# Sheet.net
KiCad netlist of a schematic drawn in Altium Designer
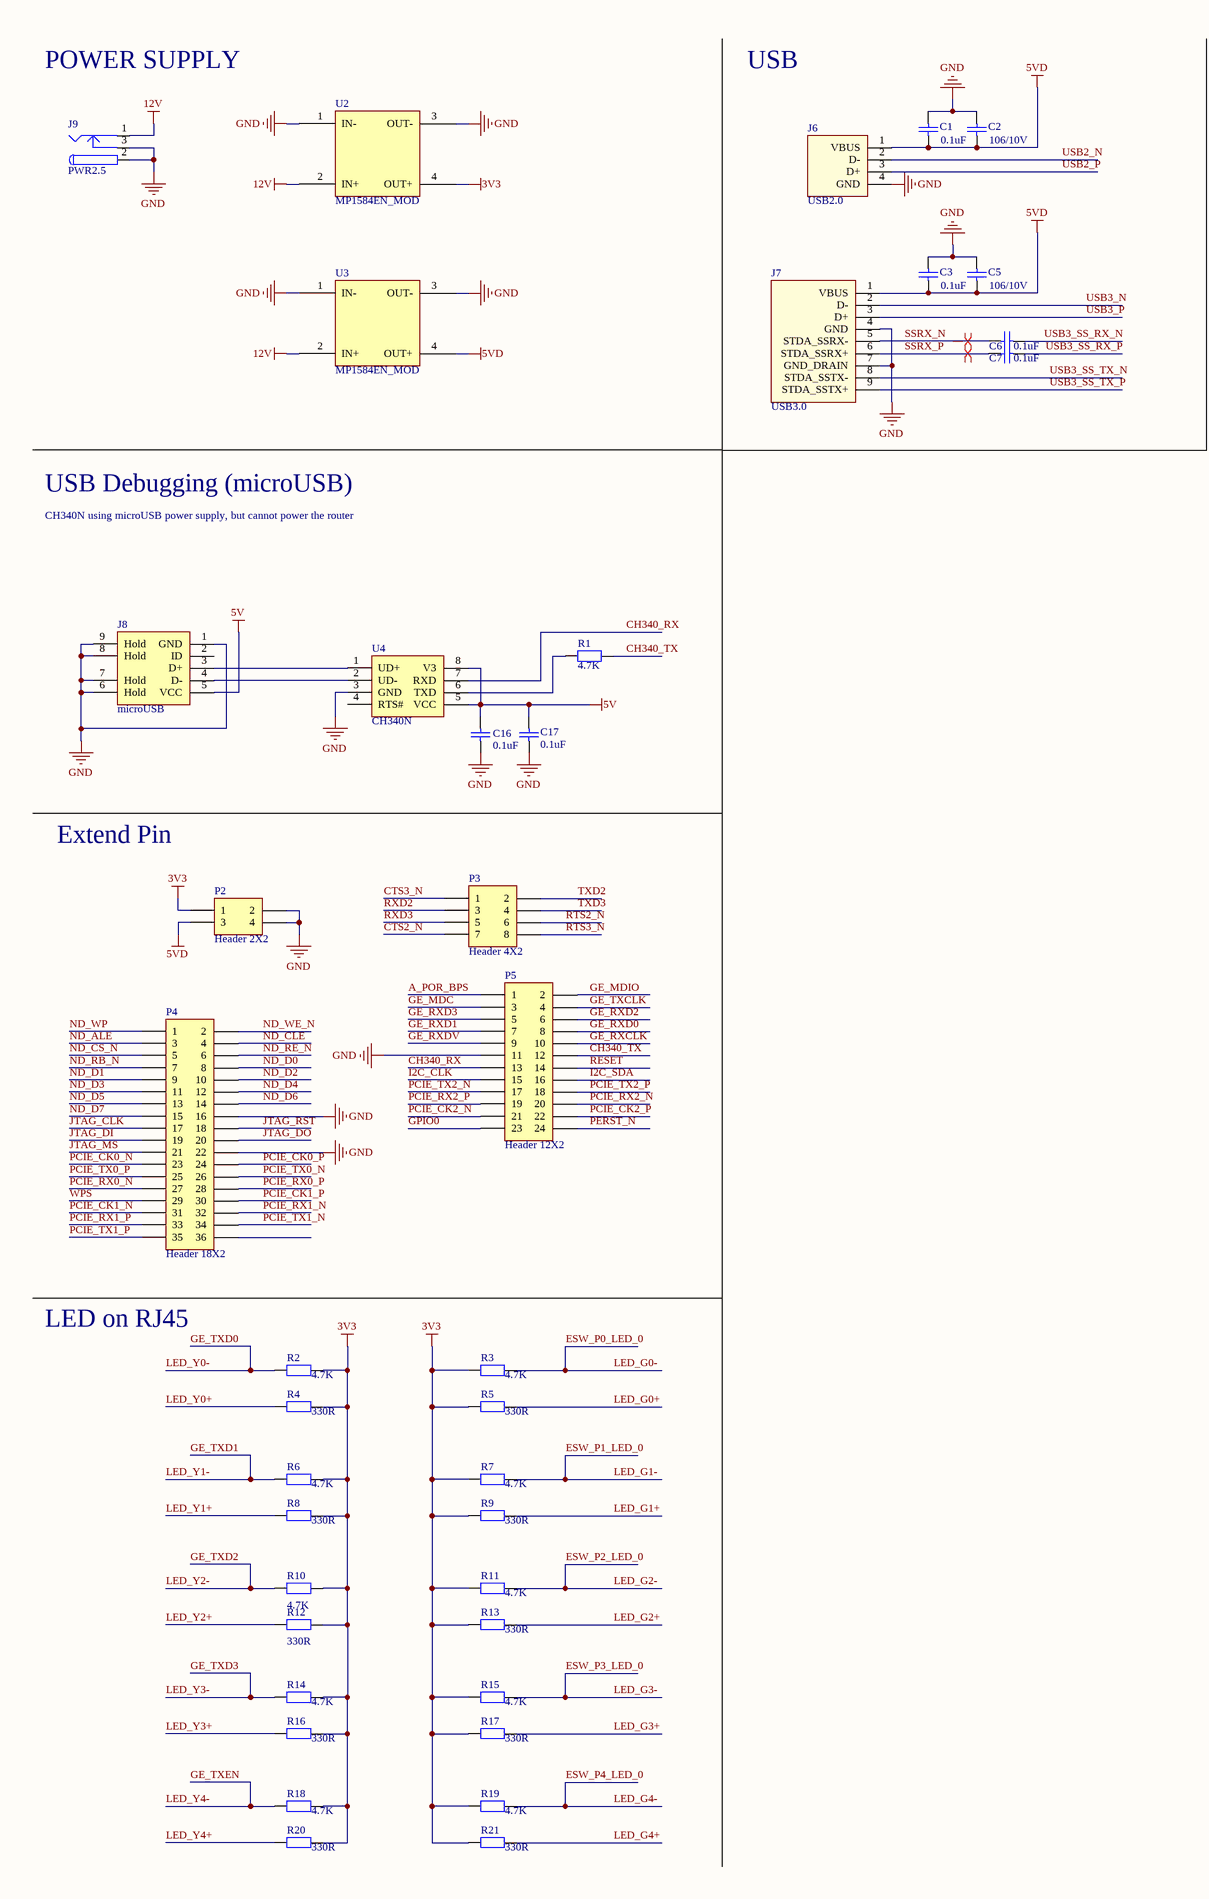
[diagram p0: Sheet.SchDoc, left]
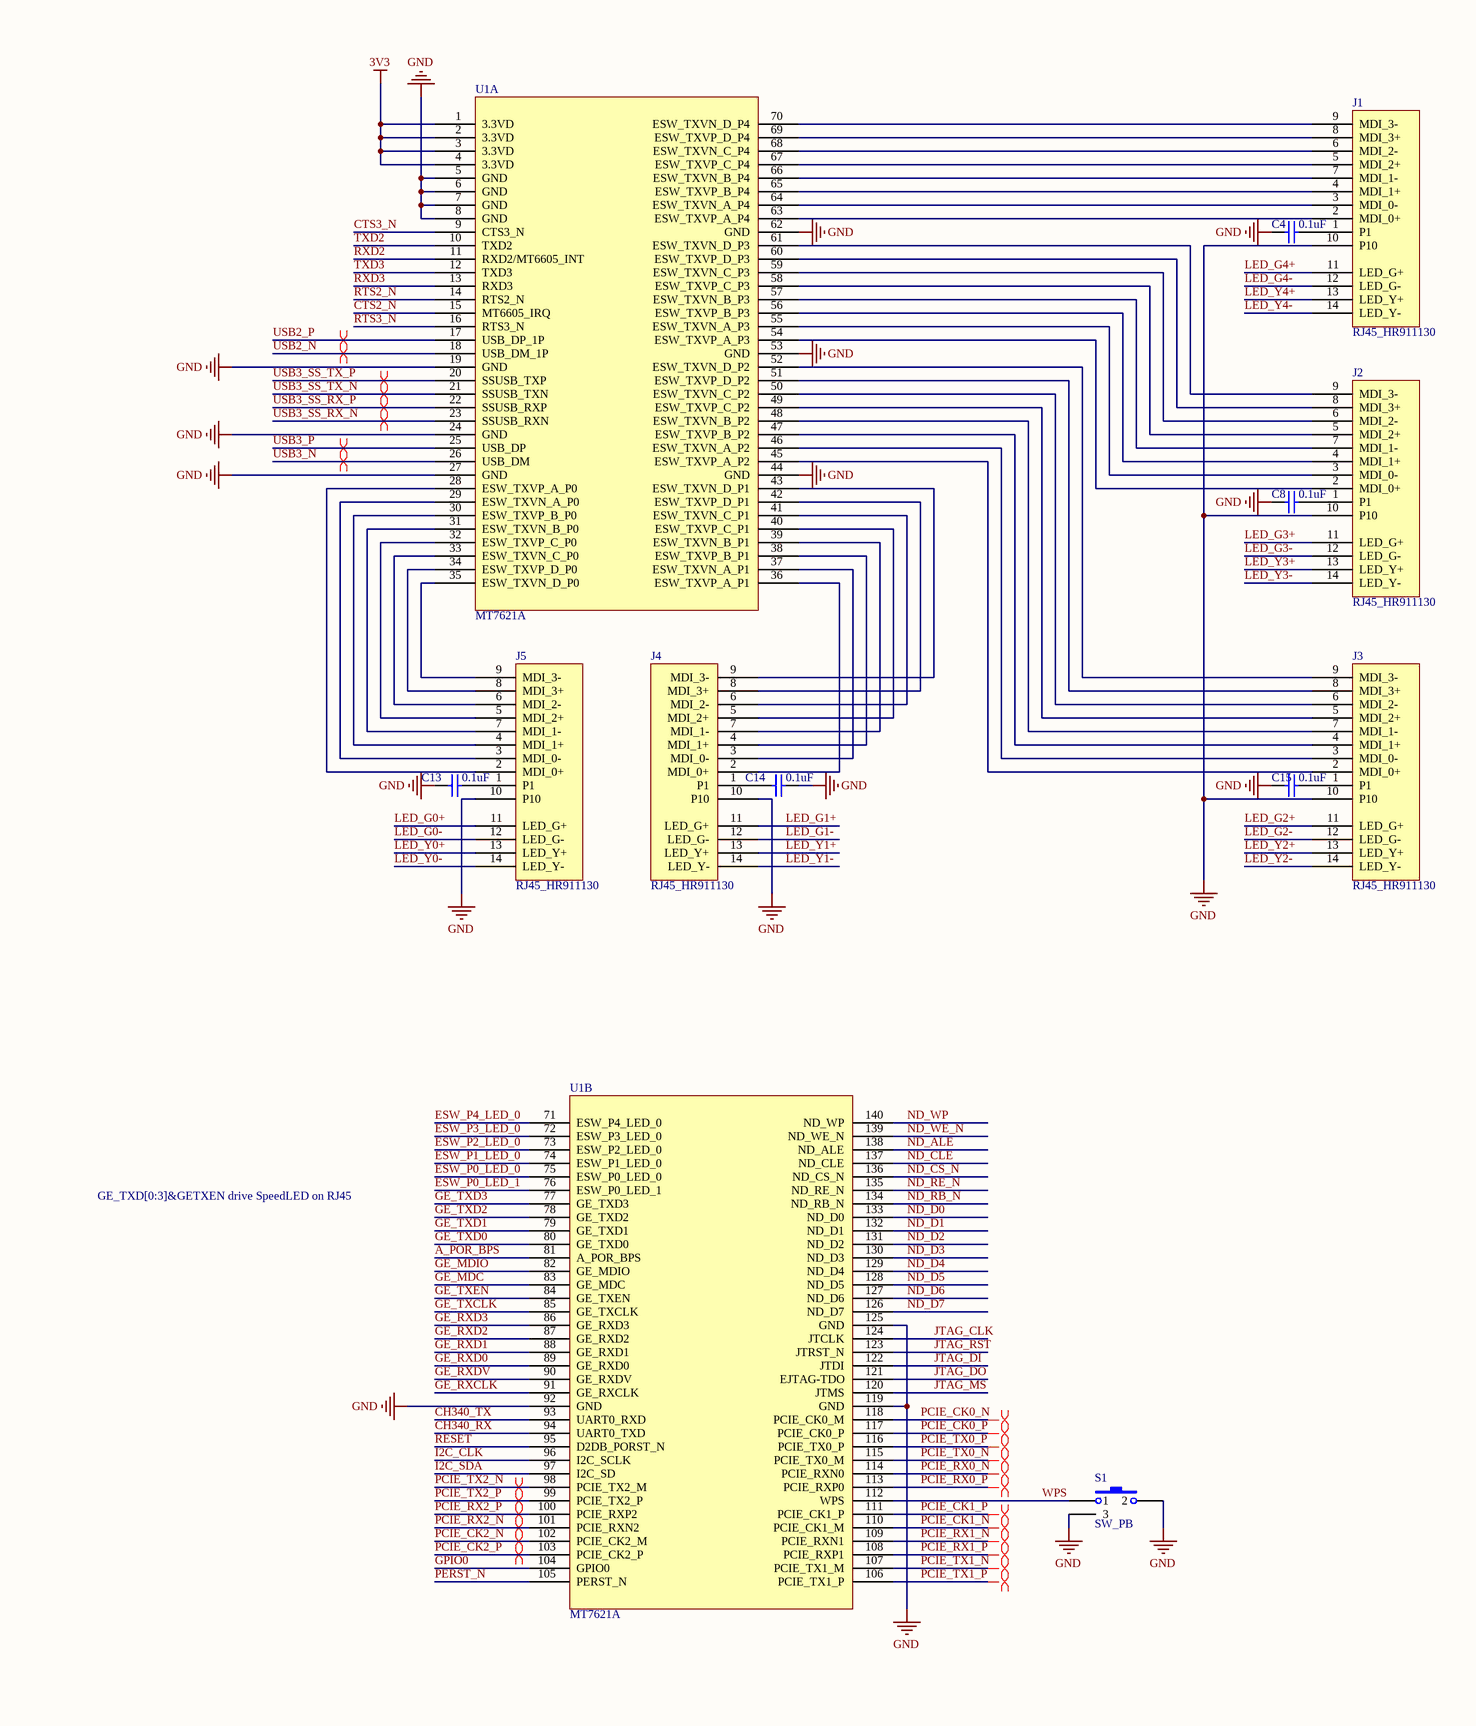
[diagram p1: Sheet.SchDoc, right]

(export (version "E")
  (design (tool "Eeschema 10.0.6"))
  (components
    (comp (ref "C1")
      (value "0.1uF")
      (footprint "6-0805")
      (description "Capacitor")
      (fields (field (name "Comment") "Cap") (field (name "PUBLISHER") "Altium Limited"))
      (libsource (lib "Miscellaneous Devices") (part "Cap"))
    )
    (comp (ref "C2")
      (value "106/10V")
      (footprint "6-0805")
      (description "Capacitor")
      (fields (field (name "Comment") "Cap") (field (name "PUBLISHER") "Altium Limited"))
      (libsource (lib "Miscellaneous Devices") (part "Cap"))
    )
    (comp (ref "C3")
      (value "0.1uF")
      (footprint "6-0805")
      (description "Capacitor")
      (fields (field (name "Comment") "Cap") (field (name "PUBLISHER") "Altium Limited"))
      (libsource (lib "Miscellaneous Devices") (part "Cap"))
    )
    (comp (ref "C4")
      (value "0.1uF")
      (footprint "6-0805")
      (description "Capacitor")
      (fields (field (name "Comment") "Cap") (field (name "PUBLISHER") "Altium Limited"))
      (libsource (lib "Miscellaneous Devices") (part "Cap"))
    )
    (comp (ref "C5")
      (value "106/10V")
      (footprint "6-0805")
      (description "Capacitor")
      (fields (field (name "Comment") "Cap") (field (name "PUBLISHER") "Altium Limited"))
      (libsource (lib "Miscellaneous Devices") (part "Cap"))
    )
    (comp (ref "C6")
      (value "0.1uF")
      (footprint "3-0603")
      (description "Capacitor")
      (fields (field (name "Comment") "Cap") (field (name "PUBLISHER") "Altium Limited"))
      (libsource (lib "Miscellaneous Devices") (part "Cap"))
    )
    (comp (ref "C7")
      (value "0.1uF")
      (footprint "3-0603")
      (description "Capacitor")
      (fields (field (name "Comment") "Cap") (field (name "PUBLISHER") "Altium Limited"))
      (libsource (lib "Miscellaneous Devices") (part "Cap"))
    )
    (comp (ref "C8")
      (value "0.1uF")
      (footprint "6-0805")
      (description "Capacitor")
      (fields (field (name "Comment") "Cap") (field (name "PUBLISHER") "Altium Limited"))
      (libsource (lib "Miscellaneous Devices") (part "Cap"))
    )
    (comp (ref "C13")
      (value "0.1uF")
      (footprint "6-0805")
      (description "Capacitor")
      (fields (field (name "Comment") "Cap") (field (name "PUBLISHER") "Altium Limited"))
      (libsource (lib "Miscellaneous Devices") (part "Cap"))
    )
    (comp (ref "C14")
      (value "0.1uF")
      (footprint "6-0805")
      (description "Capacitor")
      (fields (field (name "Comment") "Cap") (field (name "PUBLISHER") "Altium Limited"))
      (libsource (lib "Miscellaneous Devices") (part "Cap"))
    )
    (comp (ref "C15")
      (value "0.1uF")
      (footprint "6-0805")
      (description "Capacitor")
      (fields (field (name "Comment") "Cap") (field (name "PUBLISHER") "Altium Limited"))
      (libsource (lib "Miscellaneous Devices") (part "Cap"))
    )
    (comp (ref "C16")
      (value "0.1uF")
      (footprint "6-0805")
      (description "Capacitor")
      (fields (field (name "Comment") "Cap") (field (name "PUBLISHER") "Altium Limited"))
      (libsource (lib "Miscellaneous Devices") (part "Cap"))
    )
    (comp (ref "C17")
      (value "0.1uF")
      (footprint "6-0805")
      (description "Capacitor")
      (fields (field (name "Comment") "Cap") (field (name "PUBLISHER") "Altium Limited"))
      (libsource (lib "Miscellaneous Devices") (part "Cap"))
    )
    (comp (ref "J1")
      (value "RJ45_HR911130")
      (footprint "RJ45_HR911130")
      (libsource (lib "7621_cmp") (part "RJ45_HR911130"))
    )
    (comp (ref "J2")
      (value "RJ45_HR911130")
      (footprint "RJ45_HR911130")
      (libsource (lib "7621_cmp") (part "RJ45_HR911130"))
    )
    (comp (ref "J3")
      (value "RJ45_HR911130")
      (footprint "RJ45_HR911130")
      (libsource (lib "7621_cmp") (part "RJ45_HR911130"))
    )
    (comp (ref "J4")
      (value "RJ45_HR911130")
      (footprint "RJ45_HR911130")
      (libsource (lib "") (part "RJ45_HR911130_1"))
    )
    (comp (ref "J5")
      (value "RJ45_HR911130")
      (footprint "RJ45_HR911130")
      (libsource (lib "7621_cmp") (part "RJ45_HR911130"))
    )
    (comp (ref "J6") (value "USB2.0") (footprint "USB2.0") (libsource (lib "7621_cmp") (part "USB2.0")))
    (comp (ref "J7") (value "USB3.0") (footprint "USB3.0") (libsource (lib "7621_cmp") (part "USB3.0")))
    (comp (ref "J8") (value "microUSB") (footprint "MICROusb") (libsource (lib "7621_cmp") (part "microUSB")))
    (comp (ref "J9")
      (value "PWR2.5")
      (footprint "CON\\DC-JACK\\4.7")
      (libsource (lib "7621_cmp") (part "PWR2.5"))
    )
    (comp (ref "P2")
      (value "Header 2X2")
      (footprint "HDR2X2")
      (description "Header, 2-Pin, Dual row")
      (fields (field (name "PUBLISHER") "Altium Limited"))
      (libsource (lib "Miscellaneous Connectors") (part "Header 2X2"))
    )
    (comp (ref "P3")
      (value "Header 4X2")
      (footprint "HDR2X4")
      (description "Header, 4-Pin, Dual row")
      (fields (field (name "PUBLISHER") "Altium Limited"))
      (libsource (lib "Miscellaneous Connectors") (part "Header 4X2"))
    )
    (comp (ref "P4")
      (value "Header 18X2")
      (footprint "HDR2X18")
      (description "Header, 18-Pin, Dual row")
      (fields (field (name "PUBLISHER") "Altium Limited"))
      (libsource (lib "Miscellaneous Connectors") (part "Header 18X2"))
    )
    (comp (ref "P5")
      (value "Header 12X2")
      (footprint "HDR2X12")
      (description "Header, 12-Pin, Dual row")
      (fields (field (name "PUBLISHER") "Altium Limited"))
      (libsource (lib "Miscellaneous Connectors") (part "Header 12X2"))
    )
    (comp (ref "R1")
      (value "4.7K")
      (footprint "6-0805")
      (description "Resistor")
      (fields (field (name "Comment") "Res2") (field (name "PUBLISHER") "Altium Limited"))
      (libsource (lib "") (part "Res2_1"))
    )
    (comp (ref "R2")
      (value "4.7K")
      (footprint "6-0805")
      (description "Resistor")
      (fields (field (name "Comment") "Res2") (field (name "PUBLISHER") "Altium Limited"))
      (libsource (lib "Miscellaneous Devices") (part "Res2"))
    )
    (comp (ref "R3")
      (value "4.7K")
      (footprint "6-0805")
      (description "Resistor")
      (fields (field (name "Comment") "Res2") (field (name "PUBLISHER") "Altium Limited"))
      (libsource (lib "Miscellaneous Devices") (part "Res2"))
    )
    (comp (ref "R4")
      (value "330R")
      (footprint "6-0805")
      (description "Resistor")
      (fields (field (name "Comment") "Res2") (field (name "PUBLISHER") "Altium Limited"))
      (libsource (lib "Miscellaneous Devices") (part "Res2"))
    )
    (comp (ref "R5")
      (value "330R")
      (footprint "6-0805")
      (description "Resistor")
      (fields (field (name "Comment") "Res2") (field (name "PUBLISHER") "Altium Limited"))
      (libsource (lib "Miscellaneous Devices") (part "Res2"))
    )
    (comp (ref "R6")
      (value "4.7K")
      (footprint "6-0805")
      (description "Resistor")
      (fields (field (name "Comment") "Res2") (field (name "PUBLISHER") "Altium Limited"))
      (libsource (lib "Miscellaneous Devices") (part "Res2"))
    )
    (comp (ref "R7")
      (value "4.7K")
      (footprint "6-0805")
      (description "Resistor")
      (fields (field (name "Comment") "Res2") (field (name "PUBLISHER") "Altium Limited"))
      (libsource (lib "Miscellaneous Devices") (part "Res2"))
    )
    (comp (ref "R8")
      (value "330R")
      (footprint "6-0805")
      (description "Resistor")
      (fields (field (name "Comment") "Res2") (field (name "PUBLISHER") "Altium Limited"))
      (libsource (lib "Miscellaneous Devices") (part "Res2"))
    )
    (comp (ref "R9")
      (value "330R")
      (footprint "6-0805")
      (description "Resistor")
      (fields (field (name "Comment") "Res2") (field (name "PUBLISHER") "Altium Limited"))
      (libsource (lib "Miscellaneous Devices") (part "Res2"))
    )
    (comp (ref "R10")
      (value "4.7K")
      (footprint "6-0805")
      (description "Resistor")
      (fields (field (name "Comment") "Res2") (field (name "PUBLISHER") "Altium Limited"))
      (libsource (lib "Miscellaneous Devices") (part "Res2"))
    )
    (comp (ref "R11")
      (value "4.7K")
      (footprint "6-0805")
      (description "Resistor")
      (fields (field (name "Comment") "Res2") (field (name "PUBLISHER") "Altium Limited"))
      (libsource (lib "Miscellaneous Devices") (part "Res2"))
    )
    (comp (ref "R12")
      (value "330R")
      (footprint "6-0805")
      (description "Resistor")
      (fields (field (name "Comment") "Res2") (field (name "PUBLISHER") "Altium Limited"))
      (libsource (lib "Miscellaneous Devices") (part "Res2"))
    )
    (comp (ref "R13")
      (value "330R")
      (footprint "6-0805")
      (description "Resistor")
      (fields (field (name "Comment") "Res2") (field (name "PUBLISHER") "Altium Limited"))
      (libsource (lib "Miscellaneous Devices") (part "Res2"))
    )
    (comp (ref "R14")
      (value "4.7K")
      (footprint "6-0805")
      (description "Resistor")
      (fields (field (name "Comment") "Res2") (field (name "PUBLISHER") "Altium Limited"))
      (libsource (lib "Miscellaneous Devices") (part "Res2"))
    )
    (comp (ref "R15")
      (value "4.7K")
      (footprint "6-0805")
      (description "Resistor")
      (fields (field (name "Comment") "Res2") (field (name "PUBLISHER") "Altium Limited"))
      (libsource (lib "Miscellaneous Devices") (part "Res2"))
    )
    (comp (ref "R16")
      (value "330R")
      (footprint "6-0805")
      (description "Resistor")
      (fields (field (name "Comment") "Res2") (field (name "PUBLISHER") "Altium Limited"))
      (libsource (lib "Miscellaneous Devices") (part "Res2"))
    )
    (comp (ref "R17")
      (value "330R")
      (footprint "6-0805")
      (description "Resistor")
      (fields (field (name "Comment") "Res2") (field (name "PUBLISHER") "Altium Limited"))
      (libsource (lib "Miscellaneous Devices") (part "Res2"))
    )
    (comp (ref "R18")
      (value "4.7K")
      (footprint "6-0805")
      (description "Resistor")
      (fields (field (name "Comment") "Res2") (field (name "PUBLISHER") "Altium Limited"))
      (libsource (lib "Miscellaneous Devices") (part "Res2"))
    )
    (comp (ref "R19")
      (value "4.7K")
      (footprint "6-0805")
      (description "Resistor")
      (fields (field (name "Comment") "Res2") (field (name "PUBLISHER") "Altium Limited"))
      (libsource (lib "Miscellaneous Devices") (part "Res2"))
    )
    (comp (ref "R20")
      (value "330R")
      (footprint "6-0805")
      (description "Resistor")
      (fields (field (name "Comment") "Res2") (field (name "PUBLISHER") "Altium Limited"))
      (libsource (lib "Miscellaneous Devices") (part "Res2"))
    )
    (comp (ref "R21")
      (value "330R")
      (footprint "6-0805")
      (description "Resistor")
      (fields (field (name "Comment") "Res2") (field (name "PUBLISHER") "Altium Limited"))
      (libsource (lib "Miscellaneous Devices") (part "Res2"))
    )
    (comp (ref "S1") (value "SW_PB") (footprint "SW_PB") (libsource (lib "7621_cmp") (part "SW_PB")))
    (comp (ref "U1") (value "MT7621A") (footprint "HLK-7621") (libsource (lib "7621_cmp") (part "MT7621A")))
    (comp (ref "U2")
      (value "MP1584EN_MOD")
      (footprint "MP1584EN_MOD")
      (libsource (lib "7621_cmp") (part "MP1584EN_MOD"))
    )
    (comp (ref "U3")
      (value "MP1584EN_MOD")
      (footprint "MP1584EN_MOD")
      (libsource (lib "7621_cmp") (part "MP1584EN_MOD"))
    )
    (comp (ref "U4") (value "CH340N") (footprint "CH340N") (libsource (lib "7621_cmp") (part "CH340N")))
  )
  (nets
    (net (code "1") (name "/A_POR_BPS") (class "Default")
      (node (ref "P5") (pin "1") (pinfunction "1_1") (pintype "passive"))
      (node (ref "U1") (pin "81") (pinfunction "A_POR_BPS_81") (pintype "passive"))
    )
    (net (code "2") (name "/CH340_RX") (class "Default")
      (node (ref "P5") (pin "13") (pinfunction "13_13") (pintype "passive"))
      (node (ref "U1") (pin "94") (pinfunction "UART0_TXD_94") (pintype "passive"))
      (node (ref "U4") (pin "7") (pinfunction "RXD_7") (pintype "passive"))
    )
    (net (code "3") (name "/CH340_TX") (class "Default")
      (node (ref "P5") (pin "12") (pinfunction "12_12") (pintype "passive"))
      (node (ref "R1") (pin "1") (pinfunction "1_1") (pintype "passive"))
      (node (ref "U1") (pin "93") (pinfunction "UART0_RXD_93") (pintype "passive"))
    )
    (net (code "4") (name "/CTS2_N") (class "Default")
      (node (ref "P3") (pin "7") (pinfunction "7_7") (pintype "passive"))
      (node (ref "U1") (pin "15") (pinfunction "MT6605_IRQ_15") (pintype "passive"))
    )
    (net (code "5") (name "/CTS3_N") (class "Default")
      (node (ref "P3") (pin "1") (pinfunction "1_1") (pintype "passive"))
      (node (ref "U1") (pin "9") (pinfunction "CTS3_N_9") (pintype "passive"))
    )
    (net (code "6") (name "/ESW_P0_LED_0") (class "Default")
      (node (ref "J5") (pin "12") (pinfunction "LED_G-_12") (pintype "passive"))
      (node (ref "R3") (pin "2") (pinfunction "2_2") (pintype "passive"))
      (node (ref "U1") (pin "75") (pinfunction "ESW_P0_LED_0_75") (pintype "passive"))
    )
    (net (code "7") (name "/ESW_P0_LED_1") (class "Default")
      (node (ref "U1") (pin "76") (pinfunction "ESW_P0_LED_1_76") (pintype "passive"))
    )
    (net (code "8") (name "/ESW_P1_LED_0") (class "Default")
      (node (ref "J4") (pin "12") (pinfunction "LED_G-_12") (pintype "passive"))
      (node (ref "R7") (pin "2") (pinfunction "2_2") (pintype "passive"))
      (node (ref "U1") (pin "74") (pinfunction "ESW_P1_LED_0_74") (pintype "passive"))
    )
    (net (code "9") (name "/ESW_P2_LED_0") (class "Default")
      (node (ref "J3") (pin "12") (pinfunction "LED_G-_12") (pintype "passive"))
      (node (ref "R11") (pin "2") (pinfunction "2_2") (pintype "passive"))
      (node (ref "U1") (pin "73") (pinfunction "ESW_P2_LED_0_73") (pintype "passive"))
    )
    (net (code "10") (name "/ESW_P3_LED_0") (class "Default")
      (node (ref "J2") (pin "12") (pinfunction "LED_G-_12") (pintype "passive"))
      (node (ref "R15") (pin "2") (pinfunction "2_2") (pintype "passive"))
      (node (ref "U1") (pin "72") (pinfunction "ESW_P3_LED_0_72") (pintype "passive"))
    )
    (net (code "11") (name "/ESW_P4_LED_0") (class "Default")
      (node (ref "J1") (pin "12") (pinfunction "LED_G-_12") (pintype "passive"))
      (node (ref "R19") (pin "2") (pinfunction "2_2") (pintype "passive"))
      (node (ref "U1") (pin "71") (pinfunction "ESW_P4_LED_0_71") (pintype "passive"))
    )
    (net (code "12") (name "/GE_MDC") (class "Default")
      (node (ref "P5") (pin "3") (pinfunction "3_3") (pintype "passive"))
      (node (ref "U1") (pin "83") (pinfunction "GE_MDC_83") (pintype "passive"))
    )
    (net (code "13") (name "/GE_MDIO") (class "Default")
      (node (ref "P5") (pin "2") (pinfunction "2_2") (pintype "passive"))
      (node (ref "U1") (pin "82") (pinfunction "GE_MDIO_82") (pintype "passive"))
    )
    (net (code "14") (name "/GE_RXCLK") (class "Default")
      (node (ref "P5") (pin "10") (pinfunction "10_10") (pintype "passive"))
      (node (ref "U1") (pin "91") (pinfunction "GE_RXCLK_91") (pintype "passive"))
    )
    (net (code "15") (name "/GE_RXD0") (class "Default")
      (node (ref "P5") (pin "8") (pinfunction "8_8") (pintype "passive"))
      (node (ref "U1") (pin "89") (pinfunction "GE_RXD0_89") (pintype "passive"))
    )
    (net (code "16") (name "/GE_RXD1") (class "Default")
      (node (ref "P5") (pin "7") (pinfunction "7_7") (pintype "passive"))
      (node (ref "U1") (pin "88") (pinfunction "GE_RXD1_88") (pintype "passive"))
    )
    (net (code "17") (name "/GE_RXD2") (class "Default")
      (node (ref "P5") (pin "6") (pinfunction "6_6") (pintype "passive"))
      (node (ref "U1") (pin "87") (pinfunction "GE_RXD2_87") (pintype "passive"))
    )
    (net (code "18") (name "/GE_RXD3") (class "Default")
      (node (ref "P5") (pin "5") (pinfunction "5_5") (pintype "passive"))
      (node (ref "U1") (pin "86") (pinfunction "GE_RXD3_86") (pintype "passive"))
    )
    (net (code "19") (name "/GE_RXDV") (class "Default")
      (node (ref "P5") (pin "9") (pinfunction "9_9") (pintype "passive"))
      (node (ref "U1") (pin "90") (pinfunction "GE_RXDV_90") (pintype "passive"))
    )
    (net (code "20") (name "/GE_TXCLK") (class "Default")
      (node (ref "P5") (pin "4") (pinfunction "4_4") (pintype "passive"))
      (node (ref "U1") (pin "85") (pinfunction "GE_TXCLK_85") (pintype "passive"))
    )
    (net (code "21") (name "/GE_TXD0") (class "Default")
      (node (ref "J5") (pin "14") (pinfunction "LED_Y-_14") (pintype "passive"))
      (node (ref "R2") (pin "1") (pinfunction "1_1") (pintype "passive"))
      (node (ref "U1") (pin "80") (pinfunction "GE_TXD0_80") (pintype "passive"))
    )
    (net (code "22") (name "/GE_TXD1") (class "Default")
      (node (ref "J4") (pin "14") (pinfunction "LED_Y-_14") (pintype "passive"))
      (node (ref "R6") (pin "1") (pinfunction "1_1") (pintype "passive"))
      (node (ref "U1") (pin "79") (pinfunction "GE_TXD1_79") (pintype "passive"))
    )
    (net (code "23") (name "/GE_TXD2") (class "Default")
      (node (ref "J3") (pin "14") (pinfunction "LED_Y-_14") (pintype "passive"))
      (node (ref "R10") (pin "1") (pinfunction "1_1") (pintype "passive"))
      (node (ref "U1") (pin "78") (pinfunction "GE_TXD2_78") (pintype "passive"))
    )
    (net (code "24") (name "/GE_TXD3") (class "Default")
      (node (ref "J2") (pin "14") (pinfunction "LED_Y-_14") (pintype "passive"))
      (node (ref "R14") (pin "1") (pinfunction "1_1") (pintype "passive"))
      (node (ref "U1") (pin "77") (pinfunction "GE_TXD3_77") (pintype "passive"))
    )
    (net (code "25") (name "/GE_TXEN") (class "Default")
      (node (ref "J1") (pin "14") (pinfunction "LED_Y-_14") (pintype "passive"))
      (node (ref "R18") (pin "1") (pinfunction "1_1") (pintype "passive"))
      (node (ref "U1") (pin "84") (pinfunction "GE_TXEN_84") (pintype "passive"))
    )
    (net (code "26") (name "/GPIO0") (class "Default")
      (node (ref "P5") (pin "23") (pinfunction "23_23") (pintype "passive"))
      (node (ref "U1") (pin "104") (pinfunction "GPIO0_104") (pintype "passive"))
    )
    (net (code "27") (name "/I2C_CLK") (class "Default")
      (node (ref "P5") (pin "15") (pinfunction "15_15") (pintype "passive"))
      (node (ref "U1") (pin "96") (pinfunction "I2C_SCLK_96") (pintype "passive"))
    )
    (net (code "28") (name "/I2C_SDA") (class "Default")
      (node (ref "P5") (pin "16") (pinfunction "16_16") (pintype "passive"))
      (node (ref "U1") (pin "97") (pinfunction "I2C_SD_97") (pintype "passive"))
    )
    (net (code "29") (name "/JTAG_CLK") (class "Default")
      (node (ref "P4") (pin "17") (pinfunction "17_17") (pintype "passive"))
      (node (ref "U1") (pin "124") (pinfunction "JTCLK_124") (pintype "passive"))
    )
    (net (code "30") (name "/JTAG_DI") (class "Default")
      (node (ref "P4") (pin "19") (pinfunction "19_19") (pintype "passive"))
      (node (ref "U1") (pin "122") (pinfunction "JTDI_122") (pintype "passive"))
    )
    (net (code "31") (name "/JTAG_DO") (class "Default")
      (node (ref "P4") (pin "20") (pinfunction "20_20") (pintype "passive"))
      (node (ref "U1") (pin "121") (pinfunction "EJTAG-TDO_121") (pintype "passive"))
    )
    (net (code "32") (name "/JTAG_MS") (class "Default")
      (node (ref "P4") (pin "21") (pinfunction "21_21") (pintype "passive"))
      (node (ref "U1") (pin "120") (pinfunction "JTMS_120") (pintype "passive"))
    )
    (net (code "33") (name "/JTAG_RST") (class "Default")
      (node (ref "P4") (pin "18") (pinfunction "18_18") (pintype "passive"))
      (node (ref "U1") (pin "123") (pinfunction "JTRST_N_123") (pintype "passive"))
    )
    (net (code "34") (name "/LED_G0+") (class "Default")
      (node (ref "J5") (pin "11") (pinfunction "LED_G+_11") (pintype "passive"))
      (node (ref "R5") (pin "2") (pinfunction "2_2") (pintype "passive"))
    )
    (net (code "35") (name "/LED_G1+") (class "Default")
      (node (ref "J4") (pin "11") (pinfunction "LED_G+_11") (pintype "passive"))
      (node (ref "R9") (pin "2") (pinfunction "2_2") (pintype "passive"))
    )
    (net (code "36") (name "/LED_G2+") (class "Default")
      (node (ref "J3") (pin "11") (pinfunction "LED_G+_11") (pintype "passive"))
      (node (ref "R13") (pin "2") (pinfunction "2_2") (pintype "passive"))
    )
    (net (code "37") (name "/LED_G3+") (class "Default")
      (node (ref "J2") (pin "11") (pinfunction "LED_G+_11") (pintype "passive"))
      (node (ref "R17") (pin "2") (pinfunction "2_2") (pintype "passive"))
    )
    (net (code "38") (name "/LED_G4+") (class "Default")
      (node (ref "J1") (pin "11") (pinfunction "LED_G+_11") (pintype "passive"))
      (node (ref "R21") (pin "2") (pinfunction "2_2") (pintype "passive"))
    )
    (net (code "39") (name "/LED_Y0+") (class "Default")
      (node (ref "J5") (pin "13") (pinfunction "LED_Y+_13") (pintype "passive"))
      (node (ref "R4") (pin "1") (pinfunction "1_1") (pintype "passive"))
    )
    (net (code "40") (name "/LED_Y1+") (class "Default")
      (node (ref "J4") (pin "13") (pinfunction "LED_Y+_13") (pintype "passive"))
      (node (ref "R8") (pin "1") (pinfunction "1_1") (pintype "passive"))
    )
    (net (code "41") (name "/LED_Y2+") (class "Default")
      (node (ref "J3") (pin "13") (pinfunction "LED_Y+_13") (pintype "passive"))
      (node (ref "R12") (pin "1") (pinfunction "1_1") (pintype "passive"))
    )
    (net (code "42") (name "/LED_Y3+") (class "Default")
      (node (ref "J2") (pin "13") (pinfunction "LED_Y+_13") (pintype "passive"))
      (node (ref "R16") (pin "1") (pinfunction "1_1") (pintype "passive"))
    )
    (net (code "43") (name "/LED_Y4+") (class "Default")
      (node (ref "J1") (pin "13") (pinfunction "LED_Y+_13") (pintype "passive"))
      (node (ref "R20") (pin "1") (pinfunction "1_1") (pintype "passive"))
    )
    (net (code "44") (name "/ND_ALE") (class "Default")
      (node (ref "P4") (pin "3") (pinfunction "3_3") (pintype "passive"))
      (node (ref "U1") (pin "138") (pinfunction "ND_ALE_138") (pintype "passive"))
    )
    (net (code "45") (name "/ND_CLE") (class "Default")
      (node (ref "P4") (pin "4") (pinfunction "4_4") (pintype "passive"))
      (node (ref "U1") (pin "137") (pinfunction "ND_CLE_137") (pintype "passive"))
    )
    (net (code "46") (name "/ND_CS_N") (class "Default")
      (node (ref "P4") (pin "5") (pinfunction "5_5") (pintype "passive"))
      (node (ref "U1") (pin "136") (pinfunction "ND_CS_N_136") (pintype "passive"))
    )
    (net (code "47") (name "/ND_D0") (class "Default")
      (node (ref "P4") (pin "8") (pinfunction "8_8") (pintype "passive"))
      (node (ref "U1") (pin "133") (pinfunction "ND_D0_133") (pintype "passive"))
    )
    (net (code "48") (name "/ND_D1") (class "Default")
      (node (ref "P4") (pin "9") (pinfunction "9_9") (pintype "passive"))
      (node (ref "U1") (pin "132") (pinfunction "ND_D1_132") (pintype "passive"))
    )
    (net (code "49") (name "/ND_D2") (class "Default")
      (node (ref "P4") (pin "10") (pinfunction "10_10") (pintype "passive"))
      (node (ref "U1") (pin "131") (pinfunction "ND_D2_131") (pintype "passive"))
    )
    (net (code "50") (name "/ND_D3") (class "Default")
      (node (ref "P4") (pin "11") (pinfunction "11_11") (pintype "passive"))
      (node (ref "U1") (pin "130") (pinfunction "ND_D3_130") (pintype "passive"))
    )
    (net (code "51") (name "/ND_D4") (class "Default")
      (node (ref "P4") (pin "12") (pinfunction "12_12") (pintype "passive"))
      (node (ref "U1") (pin "129") (pinfunction "ND_D4_129") (pintype "passive"))
    )
    (net (code "52") (name "/ND_D5") (class "Default")
      (node (ref "P4") (pin "13") (pinfunction "13_13") (pintype "passive"))
      (node (ref "U1") (pin "128") (pinfunction "ND_D5_128") (pintype "passive"))
    )
    (net (code "53") (name "/ND_D6") (class "Default")
      (node (ref "P4") (pin "14") (pinfunction "14_14") (pintype "passive"))
      (node (ref "U1") (pin "127") (pinfunction "ND_D6_127") (pintype "passive"))
    )
    (net (code "54") (name "/ND_D7") (class "Default")
      (node (ref "P4") (pin "15") (pinfunction "15_15") (pintype "passive"))
      (node (ref "U1") (pin "126") (pinfunction "ND_D7_126") (pintype "passive"))
    )
    (net (code "55") (name "/ND_RB_N") (class "Default")
      (node (ref "P4") (pin "7") (pinfunction "7_7") (pintype "passive"))
      (node (ref "U1") (pin "134") (pinfunction "ND_RB_N_134") (pintype "passive"))
    )
    (net (code "56") (name "/ND_RE_N") (class "Default")
      (node (ref "P4") (pin "6") (pinfunction "6_6") (pintype "passive"))
      (node (ref "U1") (pin "135") (pinfunction "ND_RE_N_135") (pintype "passive"))
    )
    (net (code "57") (name "/ND_WE_N") (class "Default")
      (node (ref "P4") (pin "2") (pinfunction "2_2") (pintype "passive"))
      (node (ref "U1") (pin "139") (pinfunction "ND_WE_N_139") (pintype "passive"))
    )
    (net (code "58") (name "/ND_WP") (class "Default")
      (node (ref "P4") (pin "1") (pinfunction "1_1") (pintype "passive"))
      (node (ref "U1") (pin "140") (pinfunction "ND_WP_140") (pintype "passive"))
    )
    (net (code "59") (name "/PCIE_CK0_N") (class "Default")
      (node (ref "P4") (pin "23") (pinfunction "23_23") (pintype "passive"))
      (node (ref "U1") (pin "118") (pinfunction "PCIE_CK0_M_118") (pintype "passive"))
    )
    (net (code "60") (name "/PCIE_CK0_P") (class "Default")
      (node (ref "P4") (pin "24") (pinfunction "24_24") (pintype "passive"))
      (node (ref "U1") (pin "117") (pinfunction "PCIE_CK0_P_117") (pintype "passive"))
    )
    (net (code "61") (name "/PCIE_CK1_N") (class "Default")
      (node (ref "P4") (pin "31") (pinfunction "31_31") (pintype "passive"))
      (node (ref "U1") (pin "110") (pinfunction "PCIE_CK1_M_110") (pintype "passive"))
    )
    (net (code "62") (name "/PCIE_CK1_P") (class "Default")
      (node (ref "P4") (pin "30") (pinfunction "30_30") (pintype "passive"))
      (node (ref "U1") (pin "111") (pinfunction "PCIE_CK1_P_111") (pintype "passive"))
    )
    (net (code "63") (name "/PCIE_CK2_N") (class "Default")
      (node (ref "P5") (pin "21") (pinfunction "21_21") (pintype "passive"))
      (node (ref "U1") (pin "102") (pinfunction "PCIE_CK2_M_102") (pintype "passive"))
    )
    (net (code "64") (name "/PCIE_CK2_P") (class "Default")
      (node (ref "P5") (pin "22") (pinfunction "22_22") (pintype "passive"))
      (node (ref "U1") (pin "103") (pinfunction "PCIE_CK2_P_103") (pintype "passive"))
    )
    (net (code "65") (name "/PCIE_RX0_N") (class "Default")
      (node (ref "P4") (pin "27") (pinfunction "27_27") (pintype "passive"))
      (node (ref "U1") (pin "114") (pinfunction "PCIE_RXN0_114") (pintype "passive"))
    )
    (net (code "66") (name "/PCIE_RX0_P") (class "Default")
      (node (ref "P4") (pin "28") (pinfunction "28_28") (pintype "passive"))
      (node (ref "U1") (pin "113") (pinfunction "PCIE_RXP0_113") (pintype "passive"))
    )
    (net (code "67") (name "/PCIE_RX1_N") (class "Default")
      (node (ref "P4") (pin "32") (pinfunction "32_32") (pintype "passive"))
      (node (ref "U1") (pin "109") (pinfunction "PCIE_RXN1_109") (pintype "passive"))
    )
    (net (code "68") (name "/PCIE_RX1_P") (class "Default")
      (node (ref "P4") (pin "33") (pinfunction "33_33") (pintype "passive"))
      (node (ref "U1") (pin "108") (pinfunction "PCIE_RXP1_108") (pintype "passive"))
    )
    (net (code "69") (name "/PCIE_RX2_N") (class "Default")
      (node (ref "P5") (pin "20") (pinfunction "20_20") (pintype "passive"))
      (node (ref "U1") (pin "101") (pinfunction "PCIE_RXN2_101") (pintype "passive"))
    )
    (net (code "70") (name "/PCIE_RX2_P") (class "Default")
      (node (ref "P5") (pin "19") (pinfunction "19_19") (pintype "passive"))
      (node (ref "U1") (pin "100") (pinfunction "PCIE_RXP2_100") (pintype "passive"))
    )
    (net (code "71") (name "/PCIE_TX0_N") (class "Default")
      (node (ref "P4") (pin "26") (pinfunction "26_26") (pintype "passive"))
      (node (ref "U1") (pin "115") (pinfunction "PCIE_TX0_M_115") (pintype "passive"))
    )
    (net (code "72") (name "/PCIE_TX0_P") (class "Default")
      (node (ref "P4") (pin "25") (pinfunction "25_25") (pintype "passive"))
      (node (ref "U1") (pin "116") (pinfunction "PCIE_TX0_P_116") (pintype "passive"))
    )
    (net (code "73") (name "/PCIE_TX1_N") (class "Default")
      (node (ref "P4") (pin "34") (pinfunction "34_34") (pintype "passive"))
      (node (ref "U1") (pin "107") (pinfunction "PCIE_TX1_M_107") (pintype "passive"))
    )
    (net (code "74") (name "/PCIE_TX1_P") (class "Default")
      (node (ref "P4") (pin "35") (pinfunction "35_35") (pintype "passive"))
      (node (ref "U1") (pin "106") (pinfunction "PCIE_TX1_P_106") (pintype "passive"))
    )
    (net (code "75") (name "/PCIE_TX2_N") (class "Default")
      (node (ref "P5") (pin "17") (pinfunction "17_17") (pintype "passive"))
      (node (ref "U1") (pin "98") (pinfunction "PCIE_TX2_M_98") (pintype "passive"))
    )
    (net (code "76") (name "/PCIE_TX2_P") (class "Default")
      (node (ref "P5") (pin "18") (pinfunction "18_18") (pintype "passive"))
      (node (ref "U1") (pin "99") (pinfunction "PCIE_TX2_P_99") (pintype "passive"))
    )
    (net (code "77") (name "/PERST_N") (class "Default")
      (node (ref "P5") (pin "24") (pinfunction "24_24") (pintype "passive"))
      (node (ref "U1") (pin "105") (pinfunction "PERST_N_105") (pintype "passive"))
    )
    (net (code "78") (name "/RESET") (class "Default")
      (node (ref "P5") (pin "14") (pinfunction "14_14") (pintype "passive"))
      (node (ref "U1") (pin "95") (pinfunction "D2DB_PORST_N_95") (pintype "passive"))
    )
    (net (code "79") (name "/RTS2_N") (class "Default")
      (node (ref "P3") (pin "6") (pinfunction "6_6") (pintype "passive"))
      (node (ref "U1") (pin "14") (pinfunction "RTS2_N_14") (pintype "passive"))
    )
    (net (code "80") (name "/RTS3_N") (class "Default")
      (node (ref "P3") (pin "8") (pinfunction "8_8") (pintype "passive"))
      (node (ref "U1") (pin "16") (pinfunction "RTS3_N_16") (pintype "passive"))
    )
    (net (code "81") (name "/RXD2") (class "Default")
      (node (ref "P3") (pin "3") (pinfunction "3_3") (pintype "passive"))
      (node (ref "U1") (pin "11") (pinfunction "RXD2/MT6605_INT_11") (pintype "passive"))
    )
    (net (code "82") (name "/RXD3") (class "Default")
      (node (ref "P3") (pin "5") (pinfunction "5_5") (pintype "passive"))
      (node (ref "U1") (pin "13") (pinfunction "RXD3_13") (pintype "passive"))
    )
    (net (code "83") (name "/SSRX_N") (class "Default")
      (node (ref "C6") (pin "1") (pinfunction "1_1") (pintype "passive"))
      (node (ref "J7") (pin "5") (pinfunction "STDA_SSRX-_5") (pintype "passive"))
    )
    (net (code "84") (name "/SSRX_P") (class "Default")
      (node (ref "C7") (pin "1") (pinfunction "1_1") (pintype "passive"))
      (node (ref "J7") (pin "6") (pinfunction "STDA_SSRX+_6") (pintype "passive"))
    )
    (net (code "85") (name "/TXD2") (class "Default")
      (node (ref "P3") (pin "2") (pinfunction "2_2") (pintype "passive"))
      (node (ref "U1") (pin "10") (pinfunction "TXD2_10") (pintype "passive"))
    )
    (net (code "86") (name "/TXD3") (class "Default")
      (node (ref "P3") (pin "4") (pinfunction "4_4") (pintype "passive"))
      (node (ref "U1") (pin "12") (pinfunction "TXD3_12") (pintype "passive"))
    )
    (net (code "87") (name "/USB2_N") (class "Default")
      (node (ref "J6") (pin "2") (pinfunction "D-_2") (pintype "passive"))
      (node (ref "U1") (pin "18") (pinfunction "USB_DM_1P_18") (pintype "passive"))
    )
    (net (code "88") (name "/USB2_P") (class "Default")
      (node (ref "J6") (pin "3") (pinfunction "D+_3") (pintype "passive"))
      (node (ref "U1") (pin "17") (pinfunction "USB_DP_1P_17") (pintype "passive"))
    )
    (net (code "89") (name "/USB3_N") (class "Default")
      (node (ref "J7") (pin "2") (pinfunction "D-_2") (pintype "passive"))
      (node (ref "U1") (pin "26") (pinfunction "USB_DM_26") (pintype "passive"))
    )
    (net (code "90") (name "/USB3_P") (class "Default")
      (node (ref "J7") (pin "3") (pinfunction "D+_3") (pintype "passive"))
      (node (ref "U1") (pin "25") (pinfunction "USB_DP_25") (pintype "passive"))
    )
    (net (code "91") (name "/USB3_SS_RX_N") (class "Default")
      (node (ref "C6") (pin "2") (pinfunction "2_2") (pintype "passive"))
      (node (ref "U1") (pin "23") (pinfunction "SSUSB_RXN_23") (pintype "passive"))
    )
    (net (code "92") (name "/USB3_SS_RX_P") (class "Default")
      (node (ref "C7") (pin "2") (pinfunction "2_2") (pintype "passive"))
      (node (ref "U1") (pin "22") (pinfunction "SSUSB_RXP_22") (pintype "passive"))
    )
    (net (code "93") (name "/USB3_SS_TX_N") (class "Default")
      (node (ref "J7") (pin "8") (pinfunction "STDA_SSTX-_8") (pintype "passive"))
      (node (ref "U1") (pin "21") (pinfunction "SSUSB_TXN_21") (pintype "passive"))
    )
    (net (code "94") (name "/USB3_SS_TX_P") (class "Default")
      (node (ref "J7") (pin "9") (pinfunction "STDA_SSTX+_9") (pintype "passive"))
      (node (ref "U1") (pin "20") (pinfunction "SSUSB_TXP_20") (pintype "passive"))
    )
    (net (code "95") (name "/WPS") (class "Default")
      (node (ref "P4") (pin "29") (pinfunction "29_29") (pintype "passive"))
      (node (ref "S1") (pin "1") (pinfunction "1_1") (pintype "passive"))
      (node (ref "U1") (pin "112") (pinfunction "WPS_112") (pintype "passive"))
    )
    (net (code "96") (name "3V3") (class "Default")
      (node (ref "P2") (pin "1") (pinfunction "1_1") (pintype "passive"))
      (node (ref "R10") (pin "2") (pinfunction "2_2") (pintype "passive"))
      (node (ref "R11") (pin "1") (pinfunction "1_1") (pintype "passive"))
      (node (ref "R12") (pin "2") (pinfunction "2_2") (pintype "passive"))
      (node (ref "R13") (pin "1") (pinfunction "1_1") (pintype "passive"))
      (node (ref "R14") (pin "2") (pinfunction "2_2") (pintype "passive"))
      (node (ref "R15") (pin "1") (pinfunction "1_1") (pintype "passive"))
      (node (ref "R16") (pin "2") (pinfunction "2_2") (pintype "passive"))
      (node (ref "R17") (pin "1") (pinfunction "1_1") (pintype "passive"))
      (node (ref "R18") (pin "2") (pinfunction "2_2") (pintype "passive"))
      (node (ref "R19") (pin "1") (pinfunction "1_1") (pintype "passive"))
      (node (ref "R2") (pin "2") (pinfunction "2_2") (pintype "passive"))
      (node (ref "R20") (pin "2") (pinfunction "2_2") (pintype "passive"))
      (node (ref "R21") (pin "1") (pinfunction "1_1") (pintype "passive"))
      (node (ref "R3") (pin "1") (pinfunction "1_1") (pintype "passive"))
      (node (ref "R4") (pin "2") (pinfunction "2_2") (pintype "passive"))
      (node (ref "R5") (pin "1") (pinfunction "1_1") (pintype "passive"))
      (node (ref "R6") (pin "2") (pinfunction "2_2") (pintype "passive"))
      (node (ref "R7") (pin "1") (pinfunction "1_1") (pintype "passive"))
      (node (ref "R8") (pin "2") (pinfunction "2_2") (pintype "passive"))
      (node (ref "R9") (pin "1") (pinfunction "1_1") (pintype "passive"))
      (node (ref "U1") (pin "1") (pinfunction "3.3VD_1") (pintype "passive"))
      (node (ref "U1") (pin "2") (pinfunction "3.3VD_2") (pintype "passive"))
      (node (ref "U1") (pin "3") (pinfunction "3.3VD_3") (pintype "passive"))
      (node (ref "U1") (pin "4") (pinfunction "3.3VD_4") (pintype "passive"))
      (node (ref "U2") (pin "4") (pinfunction "OUT+_4") (pintype "passive"))
    )
    (net (code "97") (name "5V") (class "Default")
      (node (ref "C16") (pin "2") (pinfunction "2_2") (pintype "passive"))
      (node (ref "C17") (pin "1") (pinfunction "1_1") (pintype "passive"))
      (node (ref "J8") (pin "5") (pinfunction "VCC_5") (pintype "passive"))
      (node (ref "U4") (pin "5") (pinfunction "VCC_5") (pintype "passive"))
      (node (ref "U4") (pin "8") (pinfunction "V3_8") (pintype "passive"))
    )
    (net (code "98") (name "5VD") (class "Default")
      (node (ref "C1") (pin "1") (pinfunction "1_1") (pintype "passive"))
      (node (ref "C2") (pin "1") (pinfunction "1_1") (pintype "passive"))
      (node (ref "C3") (pin "1") (pinfunction "1_1") (pintype "passive"))
      (node (ref "C5") (pin "1") (pinfunction "1_1") (pintype "passive"))
      (node (ref "J6") (pin "1") (pinfunction "VBUS_1") (pintype "passive"))
      (node (ref "J7") (pin "1") (pinfunction "VBUS_1") (pintype "passive"))
      (node (ref "P2") (pin "3") (pinfunction "3_3") (pintype "passive"))
      (node (ref "U3") (pin "4") (pinfunction "OUT+_4") (pintype "passive"))
    )
    (net (code "99") (name "12V") (class "Default")
      (node (ref "J9") (pin "1") (pinfunction "1_1") (pintype "power_in"))
      (node (ref "U2") (pin "2") (pinfunction "IN+_2") (pintype "passive"))
      (node (ref "U3") (pin "2") (pinfunction "IN+_2") (pintype "passive"))
    )
    (net (code "100") (name "GND") (class "Default")
      (node (ref "C1") (pin "2") (pinfunction "2_2") (pintype "passive"))
      (node (ref "C13") (pin "2") (pinfunction "2_2") (pintype "passive"))
      (node (ref "C14") (pin "1") (pinfunction "1_1") (pintype "passive"))
      (node (ref "C15") (pin "2") (pinfunction "2_2") (pintype "passive"))
      (node (ref "C16") (pin "1") (pinfunction "1_1") (pintype "passive"))
      (node (ref "C17") (pin "2") (pinfunction "2_2") (pintype "passive"))
      (node (ref "C2") (pin "2") (pinfunction "2_2") (pintype "passive"))
      (node (ref "C3") (pin "2") (pinfunction "2_2") (pintype "passive"))
      (node (ref "C4") (pin "2") (pinfunction "2_2") (pintype "passive"))
      (node (ref "C5") (pin "2") (pinfunction "2_2") (pintype "passive"))
      (node (ref "C8") (pin "2") (pinfunction "2_2") (pintype "passive"))
      (node (ref "J1") (pin "10") (pinfunction "P10_10") (pintype "passive"))
      (node (ref "J2") (pin "10") (pinfunction "P10_10") (pintype "passive"))
      (node (ref "J3") (pin "10") (pinfunction "P10_10") (pintype "passive"))
      (node (ref "J4") (pin "10") (pinfunction "P10_10") (pintype "passive"))
      (node (ref "J5") (pin "10") (pinfunction "P10_10") (pintype "passive"))
      (node (ref "J6") (pin "4") (pinfunction "GND_4") (pintype "passive"))
      (node (ref "J7") (pin "4") (pinfunction "GND_4") (pintype "passive"))
      (node (ref "J7") (pin "7") (pinfunction "GND_DRAIN_7") (pintype "passive"))
      (node (ref "J8") (pin "1") (pinfunction "GND_1") (pintype "passive"))
      (node (ref "J8") (pin "6") (pinfunction "Hold_6") (pintype "passive"))
      (node (ref "J8") (pin "7") (pinfunction "Hold_7") (pintype "passive"))
      (node (ref "J8") (pin "8") (pinfunction "Hold_8") (pintype "passive"))
      (node (ref "J8") (pin "9") (pinfunction "Hold_9") (pintype "passive"))
      (node (ref "J9") (pin "2") (pinfunction "2_2") (pintype "power_in"))
      (node (ref "J9") (pin "3") (pinfunction "3_3") (pintype "power_in"))
      (node (ref "P2") (pin "2") (pinfunction "2_2") (pintype "passive"))
      (node (ref "P2") (pin "4") (pinfunction "4_4") (pintype "passive"))
      (node (ref "P4") (pin "16") (pinfunction "16_16") (pintype "passive"))
      (node (ref "P4") (pin "22") (pinfunction "22_22") (pintype "passive"))
      (node (ref "P5") (pin "11") (pinfunction "11_11") (pintype "passive"))
      (node (ref "S1") (pin "2") (pinfunction "2_2") (pintype "passive"))
      (node (ref "S1") (pin "3") (pinfunction "3_3") (pintype "passive"))
      (node (ref "U1") (pin "119") (pinfunction "GND_119") (pintype "passive"))
      (node (ref "U1") (pin "125") (pinfunction "GND_125") (pintype "passive"))
      (node (ref "U1") (pin "19") (pinfunction "GND_19") (pintype "passive"))
      (node (ref "U1") (pin "24") (pinfunction "GND_24") (pintype "passive"))
      (node (ref "U1") (pin "27") (pinfunction "GND_27") (pintype "passive"))
      (node (ref "U1") (pin "44") (pinfunction "GND_44") (pintype "passive"))
      (node (ref "U1") (pin "5") (pinfunction "GND_5") (pintype "passive"))
      (node (ref "U1") (pin "53") (pinfunction "GND_53") (pintype "passive"))
      (node (ref "U1") (pin "6") (pinfunction "GND_6") (pintype "passive"))
      (node (ref "U1") (pin "62") (pinfunction "GND_62") (pintype "passive"))
      (node (ref "U1") (pin "7") (pinfunction "GND_7") (pintype "passive"))
      (node (ref "U1") (pin "8") (pinfunction "GND_8") (pintype "passive"))
      (node (ref "U1") (pin "92") (pinfunction "GND_92") (pintype "passive"))
      (node (ref "U2") (pin "1") (pinfunction "IN-_1") (pintype "passive"))
      (node (ref "U2") (pin "3") (pinfunction "OUT-_3") (pintype "passive"))
      (node (ref "U3") (pin "1") (pinfunction "IN-_1") (pintype "passive"))
      (node (ref "U3") (pin "3") (pinfunction "OUT-_3") (pintype "passive"))
      (node (ref "U4") (pin "3") (pinfunction "GND_3") (pintype "passive"))
    )
    (net (code "101") (name "Net-(J1-MDI_0+)") (class "Default")
      (node (ref "J1") (pin "2") (pinfunction "MDI_0+_2") (pintype "passive"))
      (node (ref "U1") (pin "63") (pinfunction "ESW_TXVP_A_P4_63") (pintype "passive"))
    )
    (net (code "102") (name "Net-(J1-MDI_0-)") (class "Default")
      (node (ref "J1") (pin "3") (pinfunction "MDI_0-_3") (pintype "passive"))
      (node (ref "U1") (pin "64") (pinfunction "ESW_TXVN_A_P4_64") (pintype "passive"))
    )
    (net (code "103") (name "Net-(J1-MDI_1+)") (class "Default")
      (node (ref "J1") (pin "4") (pinfunction "MDI_1+_4") (pintype "passive"))
      (node (ref "U1") (pin "65") (pinfunction "ESW_TXVP_B_P4_65") (pintype "passive"))
    )
    (net (code "104") (name "Net-(J1-MDI_1-)") (class "Default")
      (node (ref "J1") (pin "7") (pinfunction "MDI_1-_7") (pintype "passive"))
      (node (ref "U1") (pin "66") (pinfunction "ESW_TXVN_B_P4_66") (pintype "passive"))
    )
    (net (code "105") (name "Net-(J1-MDI_2+)") (class "Default")
      (node (ref "J1") (pin "5") (pinfunction "MDI_2+_5") (pintype "passive"))
      (node (ref "U1") (pin "67") (pinfunction "ESW_TXVP_C_P4_67") (pintype "passive"))
    )
    (net (code "106") (name "Net-(J1-MDI_2-)") (class "Default")
      (node (ref "J1") (pin "6") (pinfunction "MDI_2-_6") (pintype "passive"))
      (node (ref "U1") (pin "68") (pinfunction "ESW_TXVN_C_P4_68") (pintype "passive"))
    )
    (net (code "107") (name "Net-(J1-MDI_3+)") (class "Default")
      (node (ref "J1") (pin "8") (pinfunction "MDI_3+_8") (pintype "passive"))
      (node (ref "U1") (pin "69") (pinfunction "ESW_TXVP_D_P4_69") (pintype "passive"))
    )
    (net (code "108") (name "Net-(J1-MDI_3-)") (class "Default")
      (node (ref "J1") (pin "9") (pinfunction "MDI_3-_9") (pintype "passive"))
      (node (ref "U1") (pin "70") (pinfunction "ESW_TXVN_D_P4_70") (pintype "passive"))
    )
    (net (code "109") (name "Net-(J1-P1)") (class "Default")
      (node (ref "C4") (pin "1") (pinfunction "1_1") (pintype "passive"))
      (node (ref "J1") (pin "1") (pinfunction "P1_1") (pintype "passive"))
    )
    (net (code "110") (name "Net-(J2-MDI_0+)") (class "Default")
      (node (ref "J2") (pin "2") (pinfunction "MDI_0+_2") (pintype "passive"))
      (node (ref "U1") (pin "54") (pinfunction "ESW_TXVP_A_P3_54") (pintype "passive"))
    )
    (net (code "111") (name "Net-(J2-MDI_0-)") (class "Default")
      (node (ref "J2") (pin "3") (pinfunction "MDI_0-_3") (pintype "passive"))
      (node (ref "U1") (pin "55") (pinfunction "ESW_TXVN_A_P3_55") (pintype "passive"))
    )
    (net (code "112") (name "Net-(J2-MDI_1+)") (class "Default")
      (node (ref "J2") (pin "4") (pinfunction "MDI_1+_4") (pintype "passive"))
      (node (ref "U1") (pin "56") (pinfunction "ESW_TXVP_B_P3_56") (pintype "passive"))
    )
    (net (code "113") (name "Net-(J2-MDI_1-)") (class "Default")
      (node (ref "J2") (pin "7") (pinfunction "MDI_1-_7") (pintype "passive"))
      (node (ref "U1") (pin "57") (pinfunction "ESW_TXVN_B_P3_57") (pintype "passive"))
    )
    (net (code "114") (name "Net-(J2-MDI_2+)") (class "Default")
      (node (ref "J2") (pin "5") (pinfunction "MDI_2+_5") (pintype "passive"))
      (node (ref "U1") (pin "58") (pinfunction "ESW_TXVP_C_P3_58") (pintype "passive"))
    )
    (net (code "115") (name "Net-(J2-MDI_2-)") (class "Default")
      (node (ref "J2") (pin "6") (pinfunction "MDI_2-_6") (pintype "passive"))
      (node (ref "U1") (pin "59") (pinfunction "ESW_TXVN_C_P3_59") (pintype "passive"))
    )
    (net (code "116") (name "Net-(J2-MDI_3+)") (class "Default")
      (node (ref "J2") (pin "8") (pinfunction "MDI_3+_8") (pintype "passive"))
      (node (ref "U1") (pin "60") (pinfunction "ESW_TXVP_D_P3_60") (pintype "passive"))
    )
    (net (code "117") (name "Net-(J2-MDI_3-)") (class "Default")
      (node (ref "J2") (pin "9") (pinfunction "MDI_3-_9") (pintype "passive"))
      (node (ref "U1") (pin "61") (pinfunction "ESW_TXVN_D_P3_61") (pintype "passive"))
    )
    (net (code "118") (name "Net-(J2-P1)") (class "Default")
      (node (ref "C8") (pin "1") (pinfunction "1_1") (pintype "passive"))
      (node (ref "J2") (pin "1") (pinfunction "P1_1") (pintype "passive"))
    )
    (net (code "119") (name "Net-(J3-MDI_0+)") (class "Default")
      (node (ref "J3") (pin "2") (pinfunction "MDI_0+_2") (pintype "passive"))
      (node (ref "U1") (pin "45") (pinfunction "ESW_TXVP_A_P2_45") (pintype "passive"))
    )
    (net (code "120") (name "Net-(J3-MDI_0-)") (class "Default")
      (node (ref "J3") (pin "3") (pinfunction "MDI_0-_3") (pintype "passive"))
      (node (ref "U1") (pin "46") (pinfunction "ESW_TXVN_A_P2_46") (pintype "passive"))
    )
    (net (code "121") (name "Net-(J3-MDI_1+)") (class "Default")
      (node (ref "J3") (pin "4") (pinfunction "MDI_1+_4") (pintype "passive"))
      (node (ref "U1") (pin "47") (pinfunction "ESW_TXVP_B_P2_47") (pintype "passive"))
    )
    (net (code "122") (name "Net-(J3-MDI_1-)") (class "Default")
      (node (ref "J3") (pin "7") (pinfunction "MDI_1-_7") (pintype "passive"))
      (node (ref "U1") (pin "48") (pinfunction "ESW_TXVN_B_P2_48") (pintype "passive"))
    )
    (net (code "123") (name "Net-(J3-MDI_2+)") (class "Default")
      (node (ref "J3") (pin "5") (pinfunction "MDI_2+_5") (pintype "passive"))
      (node (ref "U1") (pin "49") (pinfunction "ESW_TXVP_C_P2_49") (pintype "passive"))
    )
    (net (code "124") (name "Net-(J3-MDI_2-)") (class "Default")
      (node (ref "J3") (pin "6") (pinfunction "MDI_2-_6") (pintype "passive"))
      (node (ref "U1") (pin "50") (pinfunction "ESW_TXVN_C_P2_50") (pintype "passive"))
    )
    (net (code "125") (name "Net-(J3-MDI_3+)") (class "Default")
      (node (ref "J3") (pin "8") (pinfunction "MDI_3+_8") (pintype "passive"))
      (node (ref "U1") (pin "51") (pinfunction "ESW_TXVP_D_P2_51") (pintype "passive"))
    )
    (net (code "126") (name "Net-(J3-MDI_3-)") (class "Default")
      (node (ref "J3") (pin "9") (pinfunction "MDI_3-_9") (pintype "passive"))
      (node (ref "U1") (pin "52") (pinfunction "ESW_TXVN_D_P2_52") (pintype "passive"))
    )
    (net (code "127") (name "Net-(J3-P1)") (class "Default")
      (node (ref "C15") (pin "1") (pinfunction "1_1") (pintype "passive"))
      (node (ref "J3") (pin "1") (pinfunction "P1_1") (pintype "passive"))
    )
    (net (code "128") (name "Net-(J4-MDI_0+)") (class "Default")
      (node (ref "J4") (pin "2") (pinfunction "MDI_0+_2") (pintype "passive"))
      (node (ref "U1") (pin "36") (pinfunction "ESW_TXVP_A_P1_36") (pintype "passive"))
    )
    (net (code "129") (name "Net-(J4-MDI_0-)") (class "Default")
      (node (ref "J4") (pin "3") (pinfunction "MDI_0-_3") (pintype "passive"))
      (node (ref "U1") (pin "37") (pinfunction "ESW_TXVN_A_P1_37") (pintype "passive"))
    )
    (net (code "130") (name "Net-(J4-MDI_1+)") (class "Default")
      (node (ref "J4") (pin "4") (pinfunction "MDI_1+_4") (pintype "passive"))
      (node (ref "U1") (pin "38") (pinfunction "ESW_TXVP_B_P1_38") (pintype "passive"))
    )
    (net (code "131") (name "Net-(J4-MDI_1-)") (class "Default")
      (node (ref "J4") (pin "7") (pinfunction "MDI_1-_7") (pintype "passive"))
      (node (ref "U1") (pin "39") (pinfunction "ESW_TXVN_B_P1_39") (pintype "passive"))
    )
    (net (code "132") (name "Net-(J4-MDI_2+)") (class "Default")
      (node (ref "J4") (pin "5") (pinfunction "MDI_2+_5") (pintype "passive"))
      (node (ref "U1") (pin "40") (pinfunction "ESW_TXVP_C_P1_40") (pintype "passive"))
    )
    (net (code "133") (name "Net-(J4-MDI_2-)") (class "Default")
      (node (ref "J4") (pin "6") (pinfunction "MDI_2-_6") (pintype "passive"))
      (node (ref "U1") (pin "41") (pinfunction "ESW_TXVN_C_P1_41") (pintype "passive"))
    )
    (net (code "134") (name "Net-(J4-MDI_3+)") (class "Default")
      (node (ref "J4") (pin "8") (pinfunction "MDI_3+_8") (pintype "passive"))
      (node (ref "U1") (pin "42") (pinfunction "ESW_TXVP_D_P1_42") (pintype "passive"))
    )
    (net (code "135") (name "Net-(J4-MDI_3-)") (class "Default")
      (node (ref "J4") (pin "9") (pinfunction "MDI_3-_9") (pintype "passive"))
      (node (ref "U1") (pin "43") (pinfunction "ESW_TXVN_D_P1_43") (pintype "passive"))
    )
    (net (code "136") (name "Net-(J4-P1)") (class "Default")
      (node (ref "C14") (pin "2") (pinfunction "2_2") (pintype "passive"))
      (node (ref "J4") (pin "1") (pinfunction "P1_1") (pintype "passive"))
    )
    (net (code "137") (name "Net-(J5-MDI_0+)") (class "Default")
      (node (ref "J5") (pin "2") (pinfunction "MDI_0+_2") (pintype "passive"))
      (node (ref "U1") (pin "28") (pinfunction "ESW_TXVP_A_P0_28") (pintype "passive"))
    )
    (net (code "138") (name "Net-(J5-MDI_0-)") (class "Default")
      (node (ref "J5") (pin "3") (pinfunction "MDI_0-_3") (pintype "passive"))
      (node (ref "U1") (pin "29") (pinfunction "ESW_TXVN_A_P0_29") (pintype "passive"))
    )
    (net (code "139") (name "Net-(J5-MDI_1+)") (class "Default")
      (node (ref "J5") (pin "4") (pinfunction "MDI_1+_4") (pintype "passive"))
      (node (ref "U1") (pin "30") (pinfunction "ESW_TXVP_B_P0_30") (pintype "passive"))
    )
    (net (code "140") (name "Net-(J5-MDI_1-)") (class "Default")
      (node (ref "J5") (pin "7") (pinfunction "MDI_1-_7") (pintype "passive"))
      (node (ref "U1") (pin "31") (pinfunction "ESW_TXVN_B_P0_31") (pintype "passive"))
    )
    (net (code "141") (name "Net-(J5-MDI_2+)") (class "Default")
      (node (ref "J5") (pin "5") (pinfunction "MDI_2+_5") (pintype "passive"))
      (node (ref "U1") (pin "32") (pinfunction "ESW_TXVP_C_P0_32") (pintype "passive"))
    )
    (net (code "142") (name "Net-(J5-MDI_2-)") (class "Default")
      (node (ref "J5") (pin "6") (pinfunction "MDI_2-_6") (pintype "passive"))
      (node (ref "U1") (pin "33") (pinfunction "ESW_TXVN_C_P0_33") (pintype "passive"))
    )
    (net (code "143") (name "Net-(J5-MDI_3+)") (class "Default")
      (node (ref "J5") (pin "8") (pinfunction "MDI_3+_8") (pintype "passive"))
      (node (ref "U1") (pin "34") (pinfunction "ESW_TXVP_D_P0_34") (pintype "passive"))
    )
    (net (code "144") (name "Net-(J5-MDI_3-)") (class "Default")
      (node (ref "J5") (pin "9") (pinfunction "MDI_3-_9") (pintype "passive"))
      (node (ref "U1") (pin "35") (pinfunction "ESW_TXVN_D_P0_35") (pintype "passive"))
    )
    (net (code "145") (name "Net-(J5-P1)") (class "Default")
      (node (ref "C13") (pin "1") (pinfunction "1_1") (pintype "passive"))
      (node (ref "J5") (pin "1") (pinfunction "P1_1") (pintype "passive"))
    )
    (net (code "146") (name "Net-(J8-D+)") (class "Default")
      (node (ref "J8") (pin "3") (pinfunction "D+_3") (pintype "passive"))
      (node (ref "U4") (pin "1") (pinfunction "UD+_1") (pintype "passive"))
    )
    (net (code "147") (name "Net-(J8-D-)") (class "Default")
      (node (ref "J8") (pin "4") (pinfunction "D-_4") (pintype "passive"))
      (node (ref "U4") (pin "2") (pinfunction "UD-_2") (pintype "passive"))
    )
    (net (code "148") (name "Net-(U4-TXD)") (class "Default")
      (node (ref "R1") (pin "2") (pinfunction "2_2") (pintype "passive"))
      (node (ref "U4") (pin "6") (pinfunction "TXD_6") (pintype "passive"))
    )
    (net (code "149") (name "unconnected-(J8-ID-Pad2)") (class "Default")
      (node (ref "J8") (pin "2") (pinfunction "ID_2") (pintype "passive"))
    )
    (net (code "150") (name "unconnected-(P4-Pad36)") (class "Default")
      (node (ref "P4") (pin "36") (pinfunction "36_36") (pintype "passive"))
    )
    (net (code "151") (name "unconnected-(U4-RTS#-Pad4)") (class "Default")
      (node (ref "U4") (pin "4") (pinfunction "RTS#_4") (pintype "passive"))
    )
  )
)
